# SensorStation_Board_v0_4.net
KiCad netlist of a schematic drawn in EAGLE
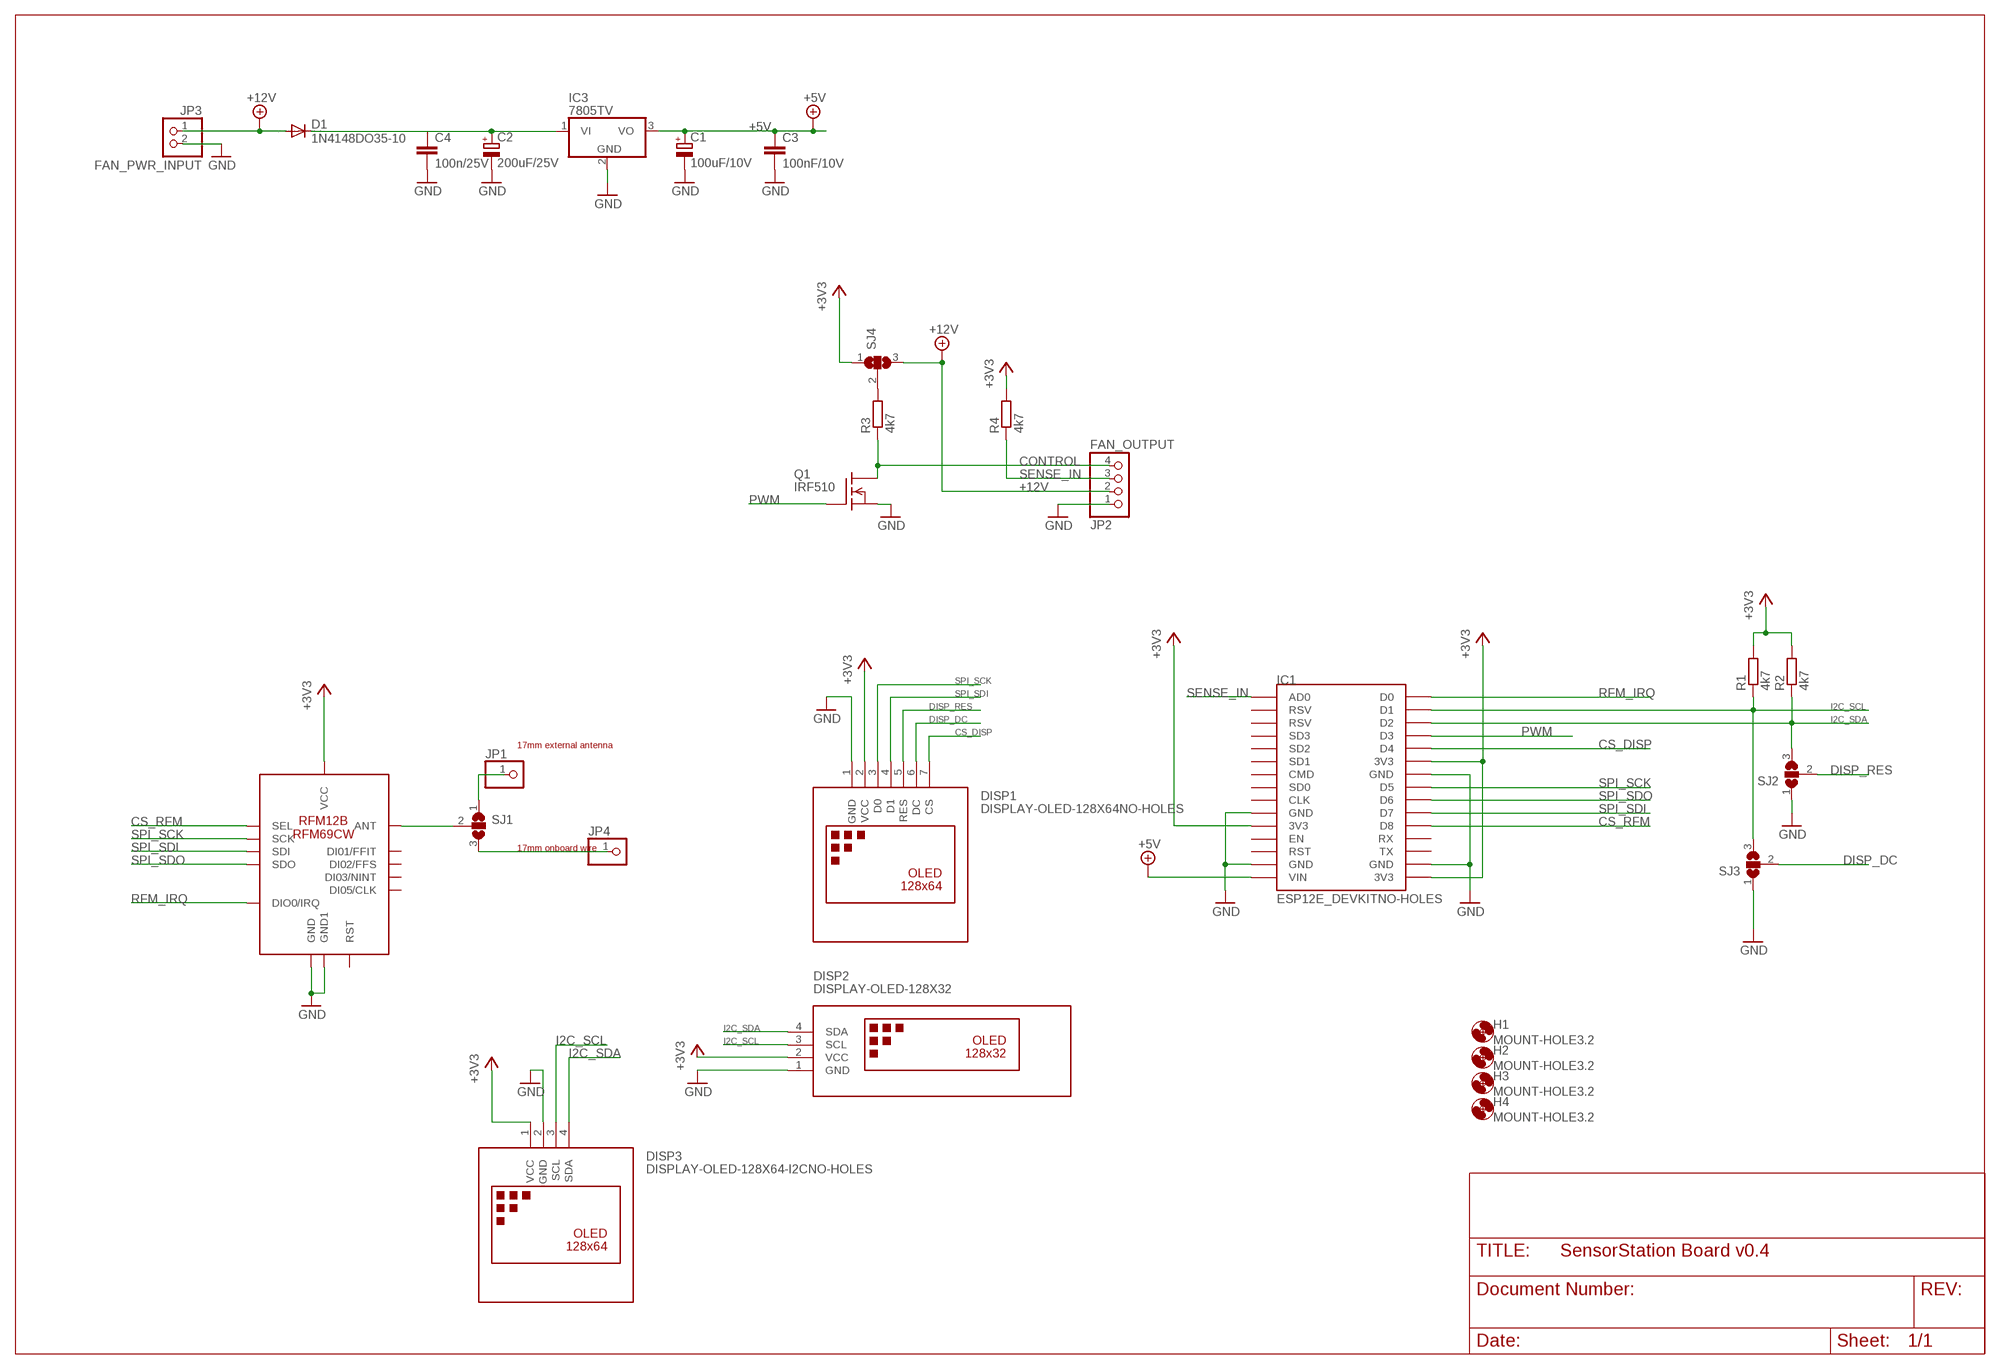
[diagram p0: schematic, sheet 1]

(export (version "E")
  (design (tool "Eeschema 10.0.6"))
  (components
    (comp (ref "C1")
      (value "100uF/10V")
      (footprint "eagle-import:E2,5-6")
      (libsource (lib "eagle-import") (part "CPOL-EUE2.5-6"))
    )
    (comp (ref "C2")
      (value "200uF/25V")
      (footprint "eagle-import:E2,5-6")
      (libsource (lib "eagle-import") (part "CPOL-EUE2.5-6"))
    )
    (comp (ref "C3")
      (value "100nF/10V")
      (footprint "eagle-import:C025-025X050")
      (libsource (lib "eagle-import") (part "C-EU025-025X050"))
    )
    (comp (ref "C4")
      (value "100n/25V")
      (footprint "eagle-import:C025-025X050")
      (libsource (lib "eagle-import") (part "C-EU025-025X050"))
    )
    (comp (ref "D1")
      (value "1N4148DO35-10")
      (footprint "eagle-import:DO35-10")
      (libsource (lib "eagle-import") (part "1N4148DO35-10"))
    )
    (comp (ref "DISP1")
      (value "DISPLAY-OLED-128X64NO-HOLES")
      (footprint "eagle-import:DISPLAY-OLED-128X64-NO-HOLES")
      (libsource (lib "eagle-import") (part "DISPLAY-OLED-128X64NO-HOLES"))
    )
    (comp (ref "DISP2")
      (value "DISPLAY-OLED-128X32")
      (footprint "eagle-import:DISPLAY-OLED-128X32")
      (libsource (lib "eagle-import") (part "DISPLAY-OLED-128X32"))
    )
    (comp (ref "DISP3")
      (value "DISPLAY-OLED-128X64-I2CNO-HOLES")
      (footprint "eagle-import:DISPLAY-OLED-128X64-I2C-NO-HOLES")
      (libsource (lib "eagle-import") (part "DISPLAY-OLED-128X64-I2CNO-HOLES"))
    )
    (comp (ref "H1")
      (value "MOUNT-HOLE3.2")
      (footprint "eagle-import:3,2")
      (libsource (lib "eagle-import") (part "MOUNT-HOLE3.2"))
    )
    (comp (ref "H2")
      (value "MOUNT-HOLE3.2")
      (footprint "eagle-import:3,2")
      (libsource (lib "eagle-import") (part "MOUNT-HOLE3.2"))
    )
    (comp (ref "H3")
      (value "MOUNT-HOLE3.2")
      (footprint "eagle-import:3,2")
      (libsource (lib "eagle-import") (part "MOUNT-HOLE3.2"))
    )
    (comp (ref "H4")
      (value "MOUNT-HOLE3.2")
      (footprint "eagle-import:3,2")
      (libsource (lib "eagle-import") (part "MOUNT-HOLE3.2"))
    )
    (comp (ref "IC1")
      (value "ESP12E_DEVKITNO-HOLES")
      (footprint "eagle-import:ESP12E_DEVKIT-NO-HOLES")
      (libsource (lib "eagle-import") (part "ESP12E_DEVKITNO-HOLES"))
    )
    (comp (ref "IC2")
      (value "RFM12B/69CW")
      (footprint "eagle-import:RFM12B_69CW")
      (libsource (lib "eagle-import") (part "RFM12B/69CW"))
    )
    (comp (ref "IC3")
      (value "7805TV")
      (footprint "eagle-import:TO220V")
      (libsource (lib "eagle-import") (part "78TV05"))
    )
    (comp (ref "JP1")
      (value "PINHD-1X1")
      (footprint "eagle-import:1X01")
      (libsource (lib "eagle-import") (part "PINHD-1X1"))
    )
    (comp (ref "JP2")
      (value "FAN_OUTPUT")
      (footprint "eagle-import:1X04")
      (libsource (lib "eagle-import") (part "PINHD-1X4"))
    )
    (comp (ref "JP3")
      (value "FAN_PWR_INPUT")
      (footprint "eagle-import:1X02")
      (libsource (lib "eagle-import") (part "PINHD-1X2"))
    )
    (comp (ref "JP4")
      (value "PINHD-1X1")
      (footprint "eagle-import:1X01")
      (libsource (lib "eagle-import") (part "PINHD-1X1"))
    )
    (comp (ref "Q1")
      (value "IRF510")
      (footprint "eagle-import:TO220")
      (libsource (lib "eagle-import") (part "IRF510"))
    )
    (comp (ref "R1")
      (value "4k7")
      (footprint "eagle-import:0204_5")
      (libsource (lib "eagle-import") (part "R-EU_0204/5"))
    )
    (comp (ref "R2")
      (value "4k7")
      (footprint "eagle-import:0204_5")
      (libsource (lib "eagle-import") (part "R-EU_0204/5"))
    )
    (comp (ref "R3")
      (value "4k7")
      (footprint "eagle-import:0204_5")
      (libsource (lib "eagle-import") (part "R-EU_0204/5"))
    )
    (comp (ref "R4")
      (value "4k7")
      (footprint "eagle-import:0204_5")
      (libsource (lib "eagle-import") (part "R-EU_0204/5"))
    )
    (comp (ref "SJ1")
      (value "SJ2W")
      (footprint "eagle-import:SJ_2")
      (libsource (lib "eagle-import") (part "SJ2W"))
    )
    (comp (ref "SJ2")
      (value "SJ2W")
      (footprint "eagle-import:SJ_2")
      (libsource (lib "eagle-import") (part "SJ2W"))
    )
    (comp (ref "SJ3")
      (value "SJ2W")
      (footprint "eagle-import:SJ_2")
      (libsource (lib "eagle-import") (part "SJ2W"))
    )
    (comp (ref "SJ4")
      (value "SJ2W")
      (footprint "eagle-import:SJ_2")
      (libsource (lib "eagle-import") (part "SJ2W"))
    )
  )
  (nets
    (net (code "1") (name "+3V3") (class "Default")
      (node (ref "DISP1") (pin "2") (pinfunction "VCC_2") (pintype "power_in"))
      (node (ref "DISP2") (pin "2") (pinfunction "VCC_2") (pintype "power_in"))
      (node (ref "DISP3") (pin "1") (pinfunction "VCC_1") (pintype "power_in"))
      (node (ref "IC1") (pin "3V3@0") (pinfunction "3V3_3V3@0") (pintype "bidirectional"))
      (node (ref "IC1") (pin "3V3@1") (pinfunction "3V3_3V3@1") (pintype "bidirectional"))
      (node (ref "IC1") (pin "3V3@2") (pinfunction "3V3_3V3@2") (pintype "bidirectional"))
      (node (ref "IC2") (pin "VDD") (pinfunction "VCC_VDD") (pintype "power_in"))
      (node (ref "R1") (pin "2") (pinfunction "2_2") (pintype "passive"))
      (node (ref "R2") (pin "2") (pinfunction "2_2") (pintype "passive"))
      (node (ref "R4") (pin "2") (pinfunction "2_2") (pintype "passive"))
      (node (ref "SJ4") (pin "1") (pinfunction "1_1") (pintype "passive"))
    )
    (net (code "2") (name "+5V") (class "Default")
      (node (ref "C1") (pin "+") (pinfunction "+_+") (pintype "passive"))
      (node (ref "C3") (pin "1") (pinfunction "1_1") (pintype "passive"))
      (node (ref "IC1") (pin "VIN") (pinfunction "VIN_VIN") (pintype "bidirectional"))
      (node (ref "IC3") (pin "3") (pinfunction "VO_3") (pintype "passive"))
    )
    (net (code "3") (name "+12V") (class "Default")
      (node (ref "D1") (pin "A") (pinfunction "A_A") (pintype "passive"))
      (node (ref "JP2") (pin "2") (pinfunction "2_2") (pintype "passive"))
      (node (ref "JP3") (pin "1") (pinfunction "1_1") (pintype "passive"))
      (node (ref "SJ4") (pin "3") (pinfunction "3_3") (pintype "passive"))
    )
    (net (code "4") (name "/CONTROL") (class "Default")
      (node (ref "JP2") (pin "4") (pinfunction "4_4") (pintype "passive"))
      (node (ref "Q1") (pin "2") (pinfunction "D_2") (pintype "passive"))
      (node (ref "R3") (pin "1") (pinfunction "1_1") (pintype "passive"))
    )
    (net (code "5") (name "/CS_DISP") (class "Default")
      (node (ref "DISP1") (pin "7") (pinfunction "CS_7") (pintype "bidirectional"))
      (node (ref "IC1") (pin "D4") (pinfunction "D4_D4") (pintype "bidirectional"))
    )
    (net (code "6") (name "/CS_RFM") (class "Default")
      (node (ref "IC1") (pin "D8") (pinfunction "D8_D8") (pintype "bidirectional"))
      (node (ref "IC2") (pin "SEL") (pinfunction "SEL_SEL") (pintype "input"))
    )
    (net (code "7") (name "/DISP_DC") (class "Default")
      (node (ref "DISP1") (pin "6") (pinfunction "DC_6") (pintype "bidirectional"))
      (node (ref "SJ3") (pin "2") (pinfunction "2_2") (pintype "passive"))
    )
    (net (code "8") (name "/DISP_RES") (class "Default")
      (node (ref "DISP1") (pin "5") (pinfunction "RES_5") (pintype "bidirectional"))
      (node (ref "SJ2") (pin "2") (pinfunction "2_2") (pintype "passive"))
    )
    (net (code "9") (name "/I2C_SCL") (class "Default")
      (node (ref "DISP2") (pin "3") (pinfunction "SCL_3") (pintype "bidirectional"))
      (node (ref "DISP3") (pin "3") (pinfunction "SCL_3") (pintype "bidirectional"))
      (node (ref "IC1") (pin "D1") (pinfunction "D1_D1") (pintype "bidirectional"))
      (node (ref "R1") (pin "1") (pinfunction "1_1") (pintype "passive"))
      (node (ref "SJ3") (pin "3") (pinfunction "3_3") (pintype "passive"))
    )
    (net (code "10") (name "/I2C_SDA") (class "Default")
      (node (ref "DISP2") (pin "4") (pinfunction "SDA_4") (pintype "bidirectional"))
      (node (ref "DISP3") (pin "4") (pinfunction "SDA_4") (pintype "bidirectional"))
      (node (ref "IC1") (pin "D2") (pinfunction "D2_D2") (pintype "bidirectional"))
      (node (ref "R2") (pin "1") (pinfunction "1_1") (pintype "passive"))
      (node (ref "SJ2") (pin "3") (pinfunction "3_3") (pintype "passive"))
    )
    (net (code "11") (name "/PWM") (class "Default")
      (node (ref "IC1") (pin "D3") (pinfunction "D3_D3") (pintype "bidirectional"))
      (node (ref "Q1") (pin "1") (pinfunction "G_1") (pintype "passive"))
    )
    (net (code "12") (name "/RFM_IRQ") (class "Default")
      (node (ref "IC1") (pin "D0") (pinfunction "D0_D0") (pintype "bidirectional"))
      (node (ref "IC2") (pin "IRQ") (pinfunction "DIO0/IRQ_IRQ") (pintype "open_collector"))
    )
    (net (code "13") (name "/SENSE_IN") (class "Default")
      (node (ref "IC1") (pin "AD0") (pinfunction "AD0_AD0") (pintype "bidirectional"))
      (node (ref "JP2") (pin "3") (pinfunction "3_3") (pintype "passive"))
      (node (ref "R4") (pin "1") (pinfunction "1_1") (pintype "passive"))
    )
    (net (code "14") (name "/SPI_SCK") (class "Default")
      (node (ref "DISP1") (pin "3") (pinfunction "D0_3") (pintype "bidirectional"))
      (node (ref "IC1") (pin "D5") (pinfunction "D5_D5") (pintype "bidirectional"))
      (node (ref "IC2") (pin "SCK") (pinfunction "SCK_SCK") (pintype "input"))
    )
    (net (code "15") (name "/SPI_SDI") (class "Default")
      (node (ref "DISP1") (pin "4") (pinfunction "D1_4") (pintype "bidirectional"))
      (node (ref "IC1") (pin "D7") (pinfunction "D7_D7") (pintype "bidirectional"))
      (node (ref "IC2") (pin "SDI") (pinfunction "SDI_SDI") (pintype "input"))
    )
    (net (code "16") (name "/SPI_SDO") (class "Default")
      (node (ref "IC1") (pin "D6") (pinfunction "D6_D6") (pintype "bidirectional"))
      (node (ref "IC2") (pin "SDO") (pinfunction "SDO_SDO") (pintype "output"))
    )
    (net (code "17") (name "GND") (class "Default")
      (node (ref "C1") (pin "-") (pinfunction "-_-") (pintype "passive"))
      (node (ref "C2") (pin "-") (pinfunction "-_-") (pintype "passive"))
      (node (ref "C3") (pin "2") (pinfunction "2_2") (pintype "passive"))
      (node (ref "C4") (pin "2") (pinfunction "2_2") (pintype "passive"))
      (node (ref "DISP1") (pin "1") (pinfunction "GND_1") (pintype "power_in"))
      (node (ref "DISP2") (pin "1") (pinfunction "GND_1") (pintype "power_in"))
      (node (ref "DISP3") (pin "2") (pinfunction "GND_2") (pintype "power_in"))
      (node (ref "IC1") (pin "GND@0") (pinfunction "GND_GND@0") (pintype "bidirectional"))
      (node (ref "IC1") (pin "GND@1") (pinfunction "GND_GND@1") (pintype "bidirectional"))
      (node (ref "IC1") (pin "GND@2") (pinfunction "GND_GND@2") (pintype "bidirectional"))
      (node (ref "IC1") (pin "GND@3") (pinfunction "GND_GND@3") (pintype "bidirectional"))
      (node (ref "IC2") (pin "GND") (pinfunction "GND_GND") (pintype "power_in"))
      (node (ref "IC2") (pin "GND1") (pinfunction "GND1_GND1") (pintype "power_in"))
      (node (ref "IC3") (pin "2") (pinfunction "GND_2") (pintype "passive"))
      (node (ref "JP2") (pin "1") (pinfunction "1_1") (pintype "passive"))
      (node (ref "JP3") (pin "2") (pinfunction "2_2") (pintype "passive"))
      (node (ref "Q1") (pin "3") (pinfunction "S_3") (pintype "passive"))
      (node (ref "SJ2") (pin "1") (pinfunction "1_1") (pintype "passive"))
      (node (ref "SJ3") (pin "1") (pinfunction "1_1") (pintype "passive"))
    )
    (net (code "18") (name "Net-(IC2-PadANT)") (class "Default")
      (node (ref "IC2") (pin "ANT") (pinfunction "ANT_ANT") (pintype "passive"))
      (node (ref "SJ1") (pin "2") (pinfunction "2_2") (pintype "passive"))
    )
    (net (code "19") (name "Net-(IC3-VI)") (class "Default")
      (node (ref "C2") (pin "+") (pinfunction "+_+") (pintype "passive"))
      (node (ref "C4") (pin "1") (pinfunction "1_1") (pintype "passive"))
      (node (ref "D1") (pin "C") (pinfunction "C_C") (pintype "passive"))
      (node (ref "IC3") (pin "1") (pinfunction "VI_1") (pintype "input"))
    )
    (net (code "20") (name "Net-(JP1-Pad1)") (class "Default")
      (node (ref "JP1") (pin "1") (pinfunction "1_1") (pintype "passive"))
      (node (ref "SJ1") (pin "1") (pinfunction "1_1") (pintype "passive"))
    )
    (net (code "21") (name "Net-(JP4-Pad1)") (class "Default")
      (node (ref "JP4") (pin "1") (pinfunction "1_1") (pintype "passive"))
      (node (ref "SJ1") (pin "3") (pinfunction "3_3") (pintype "passive"))
    )
    (net (code "22") (name "Net-(R3-Pad2)") (class "Default")
      (node (ref "R3") (pin "2") (pinfunction "2_2") (pintype "passive"))
      (node (ref "SJ4") (pin "2") (pinfunction "2_2") (pintype "passive"))
    )
    (net (code "23") (name "unconnected-(IC1-PadCLK)") (class "Default")
      (node (ref "IC1") (pin "CLK") (pinfunction "CLK_CLK") (pintype "bidirectional"))
    )
    (net (code "24") (name "unconnected-(IC1-PadCMD)") (class "Default")
      (node (ref "IC1") (pin "CMD") (pinfunction "CMD_CMD") (pintype "bidirectional"))
    )
    (net (code "25") (name "unconnected-(IC1-PadEN)") (class "Default")
      (node (ref "IC1") (pin "EN") (pinfunction "EN_EN") (pintype "bidirectional"))
    )
    (net (code "26") (name "unconnected-(IC1-PadRST)") (class "Default")
      (node (ref "IC1") (pin "RST") (pinfunction "RST_RST") (pintype "bidirectional"))
    )
    (net (code "27") (name "unconnected-(IC1-PadRX)") (class "Default")
      (node (ref "IC1") (pin "RX") (pinfunction "RX_RX") (pintype "bidirectional"))
    )
    (net (code "28") (name "unconnected-(IC1-PadSD0)") (class "Default")
      (node (ref "IC1") (pin "SD0") (pinfunction "SD0_SD0") (pintype "bidirectional"))
    )
    (net (code "29") (name "unconnected-(IC1-PadSD1)") (class "Default")
      (node (ref "IC1") (pin "SD1") (pinfunction "SD1_SD1") (pintype "bidirectional"))
    )
    (net (code "30") (name "unconnected-(IC1-PadSD2)") (class "Default")
      (node (ref "IC1") (pin "SD2") (pinfunction "SD2_SD2") (pintype "bidirectional"))
    )
    (net (code "31") (name "unconnected-(IC1-PadSD3)") (class "Default")
      (node (ref "IC1") (pin "SD3") (pinfunction "SD3_SD3") (pintype "bidirectional"))
    )
    (net (code "32") (name "unconnected-(IC1-PadTX)") (class "Default")
      (node (ref "IC1") (pin "TX") (pinfunction "TX_TX") (pintype "bidirectional"))
    )
    (net (code "33") (name "unconnected-(IC1-RSV-PadRSV@0)") (class "Default")
      (node (ref "IC1") (pin "RSV@0") (pinfunction "RSV_RSV@0") (pintype "bidirectional"))
    )
    (net (code "34") (name "unconnected-(IC1-RSV-PadRSV@1)") (class "Default")
      (node (ref "IC1") (pin "RSV@1") (pinfunction "RSV_RSV@1") (pintype "bidirectional"))
    )
    (net (code "35") (name "unconnected-(IC2-DI01{slash}FFIT-PadFFIT)") (class "Default")
      (node (ref "IC2") (pin "FFIT") (pinfunction "DI01/FFIT_FFIT") (pintype "passive"))
    )
    (net (code "36") (name "unconnected-(IC2-DI02{slash}FFS-PadFFS)") (class "Default")
      (node (ref "IC2") (pin "FFS") (pinfunction "DI02/FFS_FFS") (pintype "bidirectional"))
    )
    (net (code "37") (name "unconnected-(IC2-DI03{slash}NINT-PadNINT)") (class "Default")
      (node (ref "IC2") (pin "NINT") (pinfunction "DI03/NINT_NINT") (pintype "passive"))
    )
    (net (code "38") (name "unconnected-(IC2-DI05{slash}CLK-PadCLK)") (class "Default")
      (node (ref "IC2") (pin "CLK") (pinfunction "DI05/CLK_CLK") (pintype "passive"))
    )
    (net (code "39") (name "unconnected-(IC2-PadRST)") (class "Default")
      (node (ref "IC2") (pin "RST") (pinfunction "RST_RST") (pintype "open_collector"))
    )
  )
)
